# panel6.net
KiCad netlist of a schematic drawn in Altium Designer
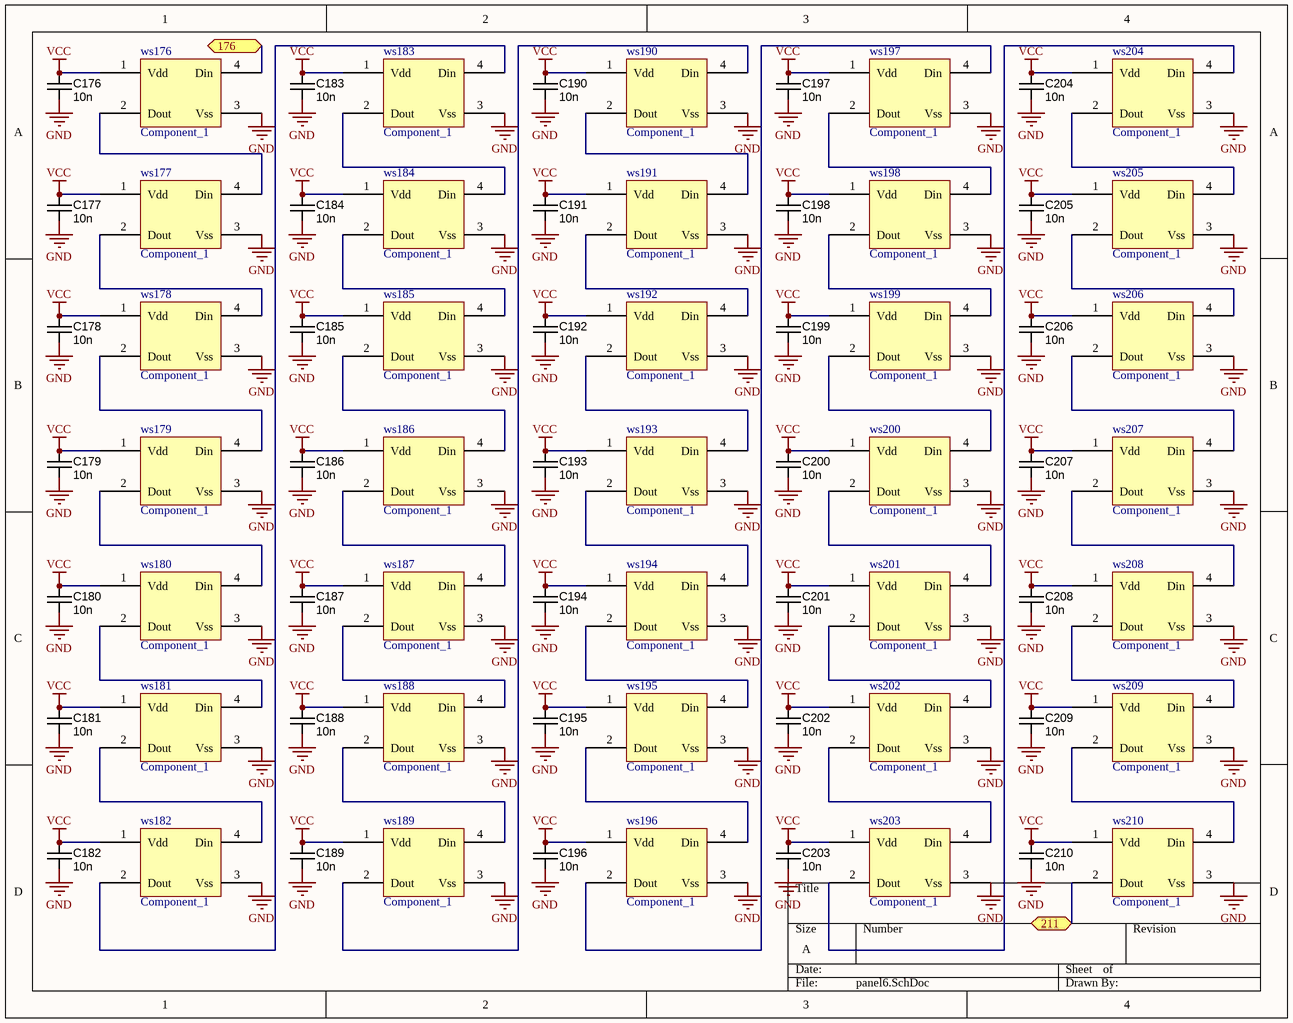
[diagram p0: panel6.SchDoc]

(export (version "E")
  (design (tool "Eeschema 10.0.6"))
  (components
    (comp (ref "C176")
      (value "10n")
      (footprint "CAPC1608X90N")
      (description "Capacitor SMD Cer 10nF 10% 100V X7R 0603")
      (fields
        (field (name "TOLERANCE") "±10%")
        (field (name "MANUFACTURER") "Murata Electronics North America")
      )
      (libsource (lib "PBL - Capacitors") (part "CAPC_10n_0603_X7R_100V_10%"))
    )
    (comp (ref "C177")
      (value "10n")
      (footprint "CAPC1608X90N")
      (description "Capacitor SMD Cer 10nF 10% 100V X7R 0603")
      (fields
        (field (name "TOLERANCE") "±10%")
        (field (name "MANUFACTURER") "Murata Electronics North America")
      )
      (libsource (lib "PBL - Capacitors") (part "CAPC_10n_0603_X7R_100V_10%"))
    )
    (comp (ref "C178")
      (value "10n")
      (footprint "CAPC1608X90N")
      (description "Capacitor SMD Cer 10nF 10% 100V X7R 0603")
      (fields
        (field (name "TOLERANCE") "±10%")
        (field (name "MANUFACTURER") "Murata Electronics North America")
      )
      (libsource (lib "PBL - Capacitors") (part "CAPC_10n_0603_X7R_100V_10%"))
    )
    (comp (ref "C179")
      (value "10n")
      (footprint "CAPC1608X90N")
      (description "Capacitor SMD Cer 10nF 10% 100V X7R 0603")
      (fields
        (field (name "TOLERANCE") "±10%")
        (field (name "MANUFACTURER") "Murata Electronics North America")
      )
      (libsource (lib "PBL - Capacitors") (part "CAPC_10n_0603_X7R_100V_10%"))
    )
    (comp (ref "C180")
      (value "10n")
      (footprint "CAPC1608X90N")
      (description "Capacitor SMD Cer 10nF 10% 100V X7R 0603")
      (fields
        (field (name "TOLERANCE") "±10%")
        (field (name "MANUFACTURER") "Murata Electronics North America")
      )
      (libsource (lib "PBL - Capacitors") (part "CAPC_10n_0603_X7R_100V_10%"))
    )
    (comp (ref "C181")
      (value "10n")
      (footprint "CAPC1608X90N")
      (description "Capacitor SMD Cer 10nF 10% 100V X7R 0603")
      (fields
        (field (name "TOLERANCE") "±10%")
        (field (name "MANUFACTURER") "Murata Electronics North America")
      )
      (libsource (lib "PBL - Capacitors") (part "CAPC_10n_0603_X7R_100V_10%"))
    )
    (comp (ref "C182")
      (value "10n")
      (footprint "CAPC1608X90N")
      (description "Capacitor SMD Cer 10nF 10% 100V X7R 0603")
      (fields
        (field (name "TOLERANCE") "±10%")
        (field (name "MANUFACTURER") "Murata Electronics North America")
      )
      (libsource (lib "PBL - Capacitors") (part "CAPC_10n_0603_X7R_100V_10%"))
    )
    (comp (ref "C183")
      (value "10n")
      (footprint "CAPC1608X90N")
      (description "Capacitor SMD Cer 10nF 10% 100V X7R 0603")
      (fields
        (field (name "TOLERANCE") "±10%")
        (field (name "MANUFACTURER") "Murata Electronics North America")
      )
      (libsource (lib "PBL - Capacitors") (part "CAPC_10n_0603_X7R_100V_10%"))
    )
    (comp (ref "C184")
      (value "10n")
      (footprint "CAPC1608X90N")
      (description "Capacitor SMD Cer 10nF 10% 100V X7R 0603")
      (fields
        (field (name "TOLERANCE") "±10%")
        (field (name "MANUFACTURER") "Murata Electronics North America")
      )
      (libsource (lib "PBL - Capacitors") (part "CAPC_10n_0603_X7R_100V_10%"))
    )
    (comp (ref "C185")
      (value "10n")
      (footprint "CAPC1608X90N")
      (description "Capacitor SMD Cer 10nF 10% 100V X7R 0603")
      (fields
        (field (name "TOLERANCE") "±10%")
        (field (name "MANUFACTURER") "Murata Electronics North America")
      )
      (libsource (lib "PBL - Capacitors") (part "CAPC_10n_0603_X7R_100V_10%"))
    )
    (comp (ref "C186")
      (value "10n")
      (footprint "CAPC1608X90N")
      (description "Capacitor SMD Cer 10nF 10% 100V X7R 0603")
      (fields
        (field (name "TOLERANCE") "±10%")
        (field (name "MANUFACTURER") "Murata Electronics North America")
      )
      (libsource (lib "PBL - Capacitors") (part "CAPC_10n_0603_X7R_100V_10%"))
    )
    (comp (ref "C187")
      (value "10n")
      (footprint "CAPC1608X90N")
      (description "Capacitor SMD Cer 10nF 10% 100V X7R 0603")
      (fields
        (field (name "TOLERANCE") "±10%")
        (field (name "MANUFACTURER") "Murata Electronics North America")
      )
      (libsource (lib "PBL - Capacitors") (part "CAPC_10n_0603_X7R_100V_10%"))
    )
    (comp (ref "C188")
      (value "10n")
      (footprint "CAPC1608X90N")
      (description "Capacitor SMD Cer 10nF 10% 100V X7R 0603")
      (fields
        (field (name "TOLERANCE") "±10%")
        (field (name "MANUFACTURER") "Murata Electronics North America")
      )
      (libsource (lib "PBL - Capacitors") (part "CAPC_10n_0603_X7R_100V_10%"))
    )
    (comp (ref "C189")
      (value "10n")
      (footprint "CAPC1608X90N")
      (description "Capacitor SMD Cer 10nF 10% 100V X7R 0603")
      (fields
        (field (name "TOLERANCE") "±10%")
        (field (name "MANUFACTURER") "Murata Electronics North America")
      )
      (libsource (lib "PBL - Capacitors") (part "CAPC_10n_0603_X7R_100V_10%"))
    )
    (comp (ref "C190")
      (value "10n")
      (footprint "CAPC1608X90N")
      (description "Capacitor SMD Cer 10nF 10% 100V X7R 0603")
      (fields
        (field (name "TOLERANCE") "±10%")
        (field (name "MANUFACTURER") "Murata Electronics North America")
      )
      (libsource (lib "PBL - Capacitors") (part "CAPC_10n_0603_X7R_100V_10%"))
    )
    (comp (ref "C191")
      (value "10n")
      (footprint "CAPC1608X90N")
      (description "Capacitor SMD Cer 10nF 10% 100V X7R 0603")
      (fields
        (field (name "TOLERANCE") "±10%")
        (field (name "MANUFACTURER") "Murata Electronics North America")
      )
      (libsource (lib "PBL - Capacitors") (part "CAPC_10n_0603_X7R_100V_10%"))
    )
    (comp (ref "C192")
      (value "10n")
      (footprint "CAPC1608X90N")
      (description "Capacitor SMD Cer 10nF 10% 100V X7R 0603")
      (fields
        (field (name "TOLERANCE") "±10%")
        (field (name "MANUFACTURER") "Murata Electronics North America")
      )
      (libsource (lib "PBL - Capacitors") (part "CAPC_10n_0603_X7R_100V_10%"))
    )
    (comp (ref "C193")
      (value "10n")
      (footprint "CAPC1608X90N")
      (description "Capacitor SMD Cer 10nF 10% 100V X7R 0603")
      (fields
        (field (name "TOLERANCE") "±10%")
        (field (name "MANUFACTURER") "Murata Electronics North America")
      )
      (libsource (lib "PBL - Capacitors") (part "CAPC_10n_0603_X7R_100V_10%"))
    )
    (comp (ref "C194")
      (value "10n")
      (footprint "CAPC1608X90N")
      (description "Capacitor SMD Cer 10nF 10% 100V X7R 0603")
      (fields
        (field (name "TOLERANCE") "±10%")
        (field (name "MANUFACTURER") "Murata Electronics North America")
      )
      (libsource (lib "PBL - Capacitors") (part "CAPC_10n_0603_X7R_100V_10%"))
    )
    (comp (ref "C195")
      (value "10n")
      (footprint "CAPC1608X90N")
      (description "Capacitor SMD Cer 10nF 10% 100V X7R 0603")
      (fields
        (field (name "TOLERANCE") "±10%")
        (field (name "MANUFACTURER") "Murata Electronics North America")
      )
      (libsource (lib "PBL - Capacitors") (part "CAPC_10n_0603_X7R_100V_10%"))
    )
    (comp (ref "C196")
      (value "10n")
      (footprint "CAPC1608X90N")
      (description "Capacitor SMD Cer 10nF 10% 100V X7R 0603")
      (fields
        (field (name "TOLERANCE") "±10%")
        (field (name "MANUFACTURER") "Murata Electronics North America")
      )
      (libsource (lib "PBL - Capacitors") (part "CAPC_10n_0603_X7R_100V_10%"))
    )
    (comp (ref "C197")
      (value "10n")
      (footprint "CAPC1608X90N")
      (description "Capacitor SMD Cer 10nF 10% 100V X7R 0603")
      (fields
        (field (name "TOLERANCE") "±10%")
        (field (name "MANUFACTURER") "Murata Electronics North America")
      )
      (libsource (lib "PBL - Capacitors") (part "CAPC_10n_0603_X7R_100V_10%"))
    )
    (comp (ref "C198")
      (value "10n")
      (footprint "CAPC1608X90N")
      (description "Capacitor SMD Cer 10nF 10% 100V X7R 0603")
      (fields
        (field (name "TOLERANCE") "±10%")
        (field (name "MANUFACTURER") "Murata Electronics North America")
      )
      (libsource (lib "PBL - Capacitors") (part "CAPC_10n_0603_X7R_100V_10%"))
    )
    (comp (ref "C199")
      (value "10n")
      (footprint "CAPC1608X90N")
      (description "Capacitor SMD Cer 10nF 10% 100V X7R 0603")
      (fields
        (field (name "TOLERANCE") "±10%")
        (field (name "MANUFACTURER") "Murata Electronics North America")
      )
      (libsource (lib "PBL - Capacitors") (part "CAPC_10n_0603_X7R_100V_10%"))
    )
    (comp (ref "C200")
      (value "10n")
      (footprint "CAPC1608X90N")
      (description "Capacitor SMD Cer 10nF 10% 100V X7R 0603")
      (fields
        (field (name "TOLERANCE") "±10%")
        (field (name "MANUFACTURER") "Murata Electronics North America")
      )
      (libsource (lib "PBL - Capacitors") (part "CAPC_10n_0603_X7R_100V_10%"))
    )
    (comp (ref "C201")
      (value "10n")
      (footprint "CAPC1608X90N")
      (description "Capacitor SMD Cer 10nF 10% 100V X7R 0603")
      (fields
        (field (name "TOLERANCE") "±10%")
        (field (name "MANUFACTURER") "Murata Electronics North America")
      )
      (libsource (lib "PBL - Capacitors") (part "CAPC_10n_0603_X7R_100V_10%"))
    )
    (comp (ref "C202")
      (value "10n")
      (footprint "CAPC1608X90N")
      (description "Capacitor SMD Cer 10nF 10% 100V X7R 0603")
      (fields
        (field (name "TOLERANCE") "±10%")
        (field (name "MANUFACTURER") "Murata Electronics North America")
      )
      (libsource (lib "PBL - Capacitors") (part "CAPC_10n_0603_X7R_100V_10%"))
    )
    (comp (ref "C203")
      (value "10n")
      (footprint "CAPC1608X90N")
      (description "Capacitor SMD Cer 10nF 10% 100V X7R 0603")
      (fields
        (field (name "TOLERANCE") "±10%")
        (field (name "MANUFACTURER") "Murata Electronics North America")
      )
      (libsource (lib "PBL - Capacitors") (part "CAPC_10n_0603_X7R_100V_10%"))
    )
    (comp (ref "C204")
      (value "10n")
      (footprint "CAPC1608X90N")
      (description "Capacitor SMD Cer 10nF 10% 100V X7R 0603")
      (fields
        (field (name "TOLERANCE") "±10%")
        (field (name "MANUFACTURER") "Murata Electronics North America")
      )
      (libsource (lib "PBL - Capacitors") (part "CAPC_10n_0603_X7R_100V_10%"))
    )
    (comp (ref "C205")
      (value "10n")
      (footprint "CAPC1608X90N")
      (description "Capacitor SMD Cer 10nF 10% 100V X7R 0603")
      (fields
        (field (name "TOLERANCE") "±10%")
        (field (name "MANUFACTURER") "Murata Electronics North America")
      )
      (libsource (lib "PBL - Capacitors") (part "CAPC_10n_0603_X7R_100V_10%"))
    )
    (comp (ref "C206")
      (value "10n")
      (footprint "CAPC1608X90N")
      (description "Capacitor SMD Cer 10nF 10% 100V X7R 0603")
      (fields
        (field (name "TOLERANCE") "±10%")
        (field (name "MANUFACTURER") "Murata Electronics North America")
      )
      (libsource (lib "PBL - Capacitors") (part "CAPC_10n_0603_X7R_100V_10%"))
    )
    (comp (ref "C207")
      (value "10n")
      (footprint "CAPC1608X90N")
      (description "Capacitor SMD Cer 10nF 10% 100V X7R 0603")
      (fields
        (field (name "TOLERANCE") "±10%")
        (field (name "MANUFACTURER") "Murata Electronics North America")
      )
      (libsource (lib "PBL - Capacitors") (part "CAPC_10n_0603_X7R_100V_10%"))
    )
    (comp (ref "C208")
      (value "10n")
      (footprint "CAPC1608X90N")
      (description "Capacitor SMD Cer 10nF 10% 100V X7R 0603")
      (fields
        (field (name "TOLERANCE") "±10%")
        (field (name "MANUFACTURER") "Murata Electronics North America")
      )
      (libsource (lib "PBL - Capacitors") (part "CAPC_10n_0603_X7R_100V_10%"))
    )
    (comp (ref "C209")
      (value "10n")
      (footprint "CAPC1608X90N")
      (description "Capacitor SMD Cer 10nF 10% 100V X7R 0603")
      (fields
        (field (name "TOLERANCE") "±10%")
        (field (name "MANUFACTURER") "Murata Electronics North America")
      )
      (libsource (lib "PBL - Capacitors") (part "CAPC_10n_0603_X7R_100V_10%"))
    )
    (comp (ref "C210")
      (value "10n")
      (footprint "CAPC1608X90N")
      (description "Capacitor SMD Cer 10nF 10% 100V X7R 0603")
      (fields
        (field (name "TOLERANCE") "±10%")
        (field (name "MANUFACTURER") "Murata Electronics North America")
      )
      (libsource (lib "PBL - Capacitors") (part "CAPC_10n_0603_X7R_100V_10%"))
    )
    (comp (ref "ws176")
      (value "Component_1")
      (footprint "SOP4")
      (libsource (lib "ws2812b") (part "Component_1"))
    )
    (comp (ref "ws177")
      (value "Component_1")
      (footprint "SOP4")
      (libsource (lib "ws2812b") (part "Component_1"))
    )
    (comp (ref "ws178")
      (value "Component_1")
      (footprint "SOP4")
      (libsource (lib "ws2812b") (part "Component_1"))
    )
    (comp (ref "ws179")
      (value "Component_1")
      (footprint "SOP4")
      (libsource (lib "ws2812b") (part "Component_1"))
    )
    (comp (ref "ws180")
      (value "Component_1")
      (footprint "SOP4")
      (libsource (lib "ws2812b") (part "Component_1"))
    )
    (comp (ref "ws181")
      (value "Component_1")
      (footprint "SOP4")
      (libsource (lib "ws2812b") (part "Component_1"))
    )
    (comp (ref "ws182")
      (value "Component_1")
      (footprint "SOP4")
      (libsource (lib "ws2812b") (part "Component_1"))
    )
    (comp (ref "ws183")
      (value "Component_1")
      (footprint "SOP4")
      (libsource (lib "ws2812b") (part "Component_1"))
    )
    (comp (ref "ws184")
      (value "Component_1")
      (footprint "SOP4")
      (libsource (lib "ws2812b") (part "Component_1"))
    )
    (comp (ref "ws185")
      (value "Component_1")
      (footprint "SOP4")
      (libsource (lib "ws2812b") (part "Component_1"))
    )
    (comp (ref "ws186")
      (value "Component_1")
      (footprint "SOP4")
      (libsource (lib "ws2812b") (part "Component_1"))
    )
    (comp (ref "ws187")
      (value "Component_1")
      (footprint "SOP4")
      (libsource (lib "ws2812b") (part "Component_1"))
    )
    (comp (ref "ws188")
      (value "Component_1")
      (footprint "SOP4")
      (libsource (lib "ws2812b") (part "Component_1"))
    )
    (comp (ref "ws189")
      (value "Component_1")
      (footprint "SOP4")
      (libsource (lib "ws2812b") (part "Component_1"))
    )
    (comp (ref "ws190")
      (value "Component_1")
      (footprint "SOP4")
      (libsource (lib "ws2812b") (part "Component_1"))
    )
    (comp (ref "ws191")
      (value "Component_1")
      (footprint "SOP4")
      (libsource (lib "ws2812b") (part "Component_1"))
    )
    (comp (ref "ws192")
      (value "Component_1")
      (footprint "SOP4")
      (libsource (lib "ws2812b") (part "Component_1"))
    )
    (comp (ref "ws193")
      (value "Component_1")
      (footprint "SOP4")
      (libsource (lib "ws2812b") (part "Component_1"))
    )
    (comp (ref "ws194")
      (value "Component_1")
      (footprint "SOP4")
      (libsource (lib "ws2812b") (part "Component_1"))
    )
    (comp (ref "ws195")
      (value "Component_1")
      (footprint "SOP4")
      (libsource (lib "ws2812b") (part "Component_1"))
    )
    (comp (ref "ws196")
      (value "Component_1")
      (footprint "SOP4")
      (libsource (lib "ws2812b") (part "Component_1"))
    )
    (comp (ref "ws197")
      (value "Component_1")
      (footprint "SOP4")
      (libsource (lib "ws2812b") (part "Component_1"))
    )
    (comp (ref "ws198")
      (value "Component_1")
      (footprint "SOP4")
      (libsource (lib "ws2812b") (part "Component_1"))
    )
    (comp (ref "ws199")
      (value "Component_1")
      (footprint "SOP4")
      (libsource (lib "ws2812b") (part "Component_1"))
    )
    (comp (ref "ws200")
      (value "Component_1")
      (footprint "SOP4")
      (libsource (lib "ws2812b") (part "Component_1"))
    )
    (comp (ref "ws201")
      (value "Component_1")
      (footprint "SOP4")
      (libsource (lib "ws2812b") (part "Component_1"))
    )
    (comp (ref "ws202")
      (value "Component_1")
      (footprint "SOP4")
      (libsource (lib "ws2812b") (part "Component_1"))
    )
    (comp (ref "ws203")
      (value "Component_1")
      (footprint "SOP4")
      (libsource (lib "ws2812b") (part "Component_1"))
    )
    (comp (ref "ws204")
      (value "Component_1")
      (footprint "SOP4")
      (libsource (lib "ws2812b") (part "Component_1"))
    )
    (comp (ref "ws205")
      (value "Component_1")
      (footprint "SOP4")
      (libsource (lib "ws2812b") (part "Component_1"))
    )
    (comp (ref "ws206")
      (value "Component_1")
      (footprint "SOP4")
      (libsource (lib "ws2812b") (part "Component_1"))
    )
    (comp (ref "ws207")
      (value "Component_1")
      (footprint "SOP4")
      (libsource (lib "ws2812b") (part "Component_1"))
    )
    (comp (ref "ws208")
      (value "Component_1")
      (footprint "SOP4")
      (libsource (lib "ws2812b") (part "Component_1"))
    )
    (comp (ref "ws209")
      (value "Component_1")
      (footprint "SOP4")
      (libsource (lib "ws2812b") (part "Component_1"))
    )
    (comp (ref "ws210")
      (value "Component_1")
      (footprint "SOP4")
      (libsource (lib "ws2812b") (part "Component_1"))
    )
  )
  (nets
    (net (code "1") (name "/176") (class "Default")
      (node (ref "ws176") (pin "4") (pinfunction "Din_4") (pintype "passive"))
    )
    (net (code "2") (name "/211") (class "Default")
      (node (ref "ws210") (pin "2") (pinfunction "Dout_2") (pintype "passive"))
    )
    (net (code "3") (name "GND") (class "Default")
      (node (ref "C176") (pin "2") (pintype "passive"))
      (node (ref "C177") (pin "2") (pintype "passive"))
      (node (ref "C178") (pin "2") (pintype "passive"))
      (node (ref "C179") (pin "2") (pintype "passive"))
      (node (ref "C180") (pin "2") (pintype "passive"))
      (node (ref "C181") (pin "2") (pintype "passive"))
      (node (ref "C182") (pin "2") (pintype "passive"))
      (node (ref "C183") (pin "2") (pintype "passive"))
      (node (ref "C184") (pin "2") (pintype "passive"))
      (node (ref "C185") (pin "2") (pintype "passive"))
      (node (ref "C186") (pin "2") (pintype "passive"))
      (node (ref "C187") (pin "2") (pintype "passive"))
      (node (ref "C188") (pin "2") (pintype "passive"))
      (node (ref "C189") (pin "2") (pintype "passive"))
      (node (ref "C190") (pin "2") (pintype "passive"))
      (node (ref "C191") (pin "2") (pintype "passive"))
      (node (ref "C192") (pin "2") (pintype "passive"))
      (node (ref "C193") (pin "2") (pintype "passive"))
      (node (ref "C194") (pin "2") (pintype "passive"))
      (node (ref "C195") (pin "2") (pintype "passive"))
      (node (ref "C196") (pin "2") (pintype "passive"))
      (node (ref "C197") (pin "2") (pintype "passive"))
      (node (ref "C198") (pin "2") (pintype "passive"))
      (node (ref "C199") (pin "2") (pintype "passive"))
      (node (ref "C200") (pin "2") (pintype "passive"))
      (node (ref "C201") (pin "2") (pintype "passive"))
      (node (ref "C202") (pin "2") (pintype "passive"))
      (node (ref "C203") (pin "2") (pintype "passive"))
      (node (ref "C204") (pin "2") (pintype "passive"))
      (node (ref "C205") (pin "2") (pintype "passive"))
      (node (ref "C206") (pin "2") (pintype "passive"))
      (node (ref "C207") (pin "2") (pintype "passive"))
      (node (ref "C208") (pin "2") (pintype "passive"))
      (node (ref "C209") (pin "2") (pintype "passive"))
      (node (ref "C210") (pin "2") (pintype "passive"))
      (node (ref "ws176") (pin "3") (pinfunction "Vss_3") (pintype "passive"))
      (node (ref "ws177") (pin "3") (pinfunction "Vss_3") (pintype "passive"))
      (node (ref "ws178") (pin "3") (pinfunction "Vss_3") (pintype "passive"))
      (node (ref "ws179") (pin "3") (pinfunction "Vss_3") (pintype "passive"))
      (node (ref "ws180") (pin "3") (pinfunction "Vss_3") (pintype "passive"))
      (node (ref "ws181") (pin "3") (pinfunction "Vss_3") (pintype "passive"))
      (node (ref "ws182") (pin "3") (pinfunction "Vss_3") (pintype "passive"))
      (node (ref "ws183") (pin "3") (pinfunction "Vss_3") (pintype "passive"))
      (node (ref "ws184") (pin "3") (pinfunction "Vss_3") (pintype "passive"))
      (node (ref "ws185") (pin "3") (pinfunction "Vss_3") (pintype "passive"))
      (node (ref "ws186") (pin "3") (pinfunction "Vss_3") (pintype "passive"))
      (node (ref "ws187") (pin "3") (pinfunction "Vss_3") (pintype "passive"))
      (node (ref "ws188") (pin "3") (pinfunction "Vss_3") (pintype "passive"))
      (node (ref "ws189") (pin "3") (pinfunction "Vss_3") (pintype "passive"))
      (node (ref "ws190") (pin "3") (pinfunction "Vss_3") (pintype "passive"))
      (node (ref "ws191") (pin "3") (pinfunction "Vss_3") (pintype "passive"))
      (node (ref "ws192") (pin "3") (pinfunction "Vss_3") (pintype "passive"))
      (node (ref "ws193") (pin "3") (pinfunction "Vss_3") (pintype "passive"))
      (node (ref "ws194") (pin "3") (pinfunction "Vss_3") (pintype "passive"))
      (node (ref "ws195") (pin "3") (pinfunction "Vss_3") (pintype "passive"))
      (node (ref "ws196") (pin "3") (pinfunction "Vss_3") (pintype "passive"))
      (node (ref "ws197") (pin "3") (pinfunction "Vss_3") (pintype "passive"))
      (node (ref "ws198") (pin "3") (pinfunction "Vss_3") (pintype "passive"))
      (node (ref "ws199") (pin "3") (pinfunction "Vss_3") (pintype "passive"))
      (node (ref "ws200") (pin "3") (pinfunction "Vss_3") (pintype "passive"))
      (node (ref "ws201") (pin "3") (pinfunction "Vss_3") (pintype "passive"))
      (node (ref "ws202") (pin "3") (pinfunction "Vss_3") (pintype "passive"))
      (node (ref "ws203") (pin "3") (pinfunction "Vss_3") (pintype "passive"))
      (node (ref "ws204") (pin "3") (pinfunction "Vss_3") (pintype "passive"))
      (node (ref "ws205") (pin "3") (pinfunction "Vss_3") (pintype "passive"))
      (node (ref "ws206") (pin "3") (pinfunction "Vss_3") (pintype "passive"))
      (node (ref "ws207") (pin "3") (pinfunction "Vss_3") (pintype "passive"))
      (node (ref "ws208") (pin "3") (pinfunction "Vss_3") (pintype "passive"))
      (node (ref "ws209") (pin "3") (pinfunction "Vss_3") (pintype "passive"))
      (node (ref "ws210") (pin "3") (pinfunction "Vss_3") (pintype "passive"))
    )
    (net (code "4") (name "Net-(ws176-Dout)") (class "Default")
      (node (ref "ws176") (pin "2") (pinfunction "Dout_2") (pintype "passive"))
      (node (ref "ws177") (pin "4") (pinfunction "Din_4") (pintype "passive"))
    )
    (net (code "5") (name "Net-(ws177-Dout)") (class "Default")
      (node (ref "ws177") (pin "2") (pinfunction "Dout_2") (pintype "passive"))
      (node (ref "ws178") (pin "4") (pinfunction "Din_4") (pintype "passive"))
    )
    (net (code "6") (name "Net-(ws178-Dout)") (class "Default")
      (node (ref "ws178") (pin "2") (pinfunction "Dout_2") (pintype "passive"))
      (node (ref "ws179") (pin "4") (pinfunction "Din_4") (pintype "passive"))
    )
    (net (code "7") (name "Net-(ws179-Dout)") (class "Default")
      (node (ref "ws179") (pin "2") (pinfunction "Dout_2") (pintype "passive"))
      (node (ref "ws180") (pin "4") (pinfunction "Din_4") (pintype "passive"))
    )
    (net (code "8") (name "Net-(ws180-Dout)") (class "Default")
      (node (ref "ws180") (pin "2") (pinfunction "Dout_2") (pintype "passive"))
      (node (ref "ws181") (pin "4") (pinfunction "Din_4") (pintype "passive"))
    )
    (net (code "9") (name "Net-(ws181-Dout)") (class "Default")
      (node (ref "ws181") (pin "2") (pinfunction "Dout_2") (pintype "passive"))
      (node (ref "ws182") (pin "4") (pinfunction "Din_4") (pintype "passive"))
    )
    (net (code "10") (name "Net-(ws182-Dout)") (class "Default")
      (node (ref "ws182") (pin "2") (pinfunction "Dout_2") (pintype "passive"))
      (node (ref "ws183") (pin "4") (pinfunction "Din_4") (pintype "passive"))
    )
    (net (code "11") (name "Net-(ws183-Dout)") (class "Default")
      (node (ref "ws183") (pin "2") (pinfunction "Dout_2") (pintype "passive"))
      (node (ref "ws184") (pin "4") (pinfunction "Din_4") (pintype "passive"))
    )
    (net (code "12") (name "Net-(ws184-Dout)") (class "Default")
      (node (ref "ws184") (pin "2") (pinfunction "Dout_2") (pintype "passive"))
      (node (ref "ws185") (pin "4") (pinfunction "Din_4") (pintype "passive"))
    )
    (net (code "13") (name "Net-(ws185-Dout)") (class "Default")
      (node (ref "ws185") (pin "2") (pinfunction "Dout_2") (pintype "passive"))
      (node (ref "ws186") (pin "4") (pinfunction "Din_4") (pintype "passive"))
    )
    (net (code "14") (name "Net-(ws186-Dout)") (class "Default")
      (node (ref "ws186") (pin "2") (pinfunction "Dout_2") (pintype "passive"))
      (node (ref "ws187") (pin "4") (pinfunction "Din_4") (pintype "passive"))
    )
    (net (code "15") (name "Net-(ws187-Dout)") (class "Default")
      (node (ref "ws187") (pin "2") (pinfunction "Dout_2") (pintype "passive"))
      (node (ref "ws188") (pin "4") (pinfunction "Din_4") (pintype "passive"))
    )
    (net (code "16") (name "Net-(ws188-Dout)") (class "Default")
      (node (ref "ws188") (pin "2") (pinfunction "Dout_2") (pintype "passive"))
      (node (ref "ws189") (pin "4") (pinfunction "Din_4") (pintype "passive"))
    )
    (net (code "17") (name "Net-(ws189-Dout)") (class "Default")
      (node (ref "ws189") (pin "2") (pinfunction "Dout_2") (pintype "passive"))
      (node (ref "ws190") (pin "4") (pinfunction "Din_4") (pintype "passive"))
    )
    (net (code "18") (name "Net-(ws190-Dout)") (class "Default")
      (node (ref "ws190") (pin "2") (pinfunction "Dout_2") (pintype "passive"))
      (node (ref "ws191") (pin "4") (pinfunction "Din_4") (pintype "passive"))
    )
    (net (code "19") (name "Net-(ws191-Dout)") (class "Default")
      (node (ref "ws191") (pin "2") (pinfunction "Dout_2") (pintype "passive"))
      (node (ref "ws192") (pin "4") (pinfunction "Din_4") (pintype "passive"))
    )
    (net (code "20") (name "Net-(ws192-Dout)") (class "Default")
      (node (ref "ws192") (pin "2") (pinfunction "Dout_2") (pintype "passive"))
      (node (ref "ws193") (pin "4") (pinfunction "Din_4") (pintype "passive"))
    )
    (net (code "21") (name "Net-(ws193-Dout)") (class "Default")
      (node (ref "ws193") (pin "2") (pinfunction "Dout_2") (pintype "passive"))
      (node (ref "ws194") (pin "4") (pinfunction "Din_4") (pintype "passive"))
    )
    (net (code "22") (name "Net-(ws194-Dout)") (class "Default")
      (node (ref "ws194") (pin "2") (pinfunction "Dout_2") (pintype "passive"))
      (node (ref "ws195") (pin "4") (pinfunction "Din_4") (pintype "passive"))
    )
    (net (code "23") (name "Net-(ws195-Dout)") (class "Default")
      (node (ref "ws195") (pin "2") (pinfunction "Dout_2") (pintype "passive"))
      (node (ref "ws196") (pin "4") (pinfunction "Din_4") (pintype "passive"))
    )
    (net (code "24") (name "Net-(ws196-Dout)") (class "Default")
      (node (ref "ws196") (pin "2") (pinfunction "Dout_2") (pintype "passive"))
      (node (ref "ws197") (pin "4") (pinfunction "Din_4") (pintype "passive"))
    )
    (net (code "25") (name "Net-(ws197-Dout)") (class "Default")
      (node (ref "ws197") (pin "2") (pinfunction "Dout_2") (pintype "passive"))
      (node (ref "ws198") (pin "4") (pinfunction "Din_4") (pintype "passive"))
    )
    (net (code "26") (name "Net-(ws198-Dout)") (class "Default")
      (node (ref "ws198") (pin "2") (pinfunction "Dout_2") (pintype "passive"))
      (node (ref "ws199") (pin "4") (pinfunction "Din_4") (pintype "passive"))
    )
    (net (code "27") (name "Net-(ws199-Dout)") (class "Default")
      (node (ref "ws199") (pin "2") (pinfunction "Dout_2") (pintype "passive"))
      (node (ref "ws200") (pin "4") (pinfunction "Din_4") (pintype "passive"))
    )
    (net (code "28") (name "Net-(ws200-Dout)") (class "Default")
      (node (ref "ws200") (pin "2") (pinfunction "Dout_2") (pintype "passive"))
      (node (ref "ws201") (pin "4") (pinfunction "Din_4") (pintype "passive"))
    )
    (net (code "29") (name "Net-(ws201-Dout)") (class "Default")
      (node (ref "ws201") (pin "2") (pinfunction "Dout_2") (pintype "passive"))
      (node (ref "ws202") (pin "4") (pinfunction "Din_4") (pintype "passive"))
    )
    (net (code "30") (name "Net-(ws202-Dout)") (class "Default")
      (node (ref "ws202") (pin "2") (pinfunction "Dout_2") (pintype "passive"))
      (node (ref "ws203") (pin "4") (pinfunction "Din_4") (pintype "passive"))
    )
    (net (code "31") (name "Net-(ws203-Dout)") (class "Default")
      (node (ref "ws203") (pin "2") (pinfunction "Dout_2") (pintype "passive"))
      (node (ref "ws204") (pin "4") (pinfunction "Din_4") (pintype "passive"))
    )
    (net (code "32") (name "Net-(ws204-Dout)") (class "Default")
      (node (ref "ws204") (pin "2") (pinfunction "Dout_2") (pintype "passive"))
      (node (ref "ws205") (pin "4") (pinfunction "Din_4") (pintype "passive"))
    )
    (net (code "33") (name "Net-(ws205-Dout)") (class "Default")
      (node (ref "ws205") (pin "2") (pinfunction "Dout_2") (pintype "passive"))
      (node (ref "ws206") (pin "4") (pinfunction "Din_4") (pintype "passive"))
    )
    (net (code "34") (name "Net-(ws206-Dout)") (class "Default")
      (node (ref "ws206") (pin "2") (pinfunction "Dout_2") (pintype "passive"))
      (node (ref "ws207") (pin "4") (pinfunction "Din_4") (pintype "passive"))
    )
    (net (code "35") (name "Net-(ws207-Dout)") (class "Default")
      (node (ref "ws207") (pin "2") (pinfunction "Dout_2") (pintype "passive"))
      (node (ref "ws208") (pin "4") (pinfunction "Din_4") (pintype "passive"))
    )
    (net (code "36") (name "Net-(ws208-Dout)") (class "Default")
      (node (ref "ws208") (pin "2") (pinfunction "Dout_2") (pintype "passive"))
      (node (ref "ws209") (pin "4") (pinfunction "Din_4") (pintype "passive"))
    )
    (net (code "37") (name "Net-(ws209-Dout)") (class "Default")
      (node (ref "ws209") (pin "2") (pinfunction "Dout_2") (pintype "passive"))
      (node (ref "ws210") (pin "4") (pinfunction "Din_4") (pintype "passive"))
    )
    (net (code "38") (name "VCC") (class "Default")
      (node (ref "C176") (pin "1") (pintype "passive"))
      (node (ref "C177") (pin "1") (pintype "passive"))
      (node (ref "C178") (pin "1") (pintype "passive"))
      (node (ref "C179") (pin "1") (pintype "passive"))
      (node (ref "C180") (pin "1") (pintype "passive"))
      (node (ref "C181") (pin "1") (pintype "passive"))
      (node (ref "C182") (pin "1") (pintype "passive"))
      (node (ref "C183") (pin "1") (pintype "passive"))
      (node (ref "C184") (pin "1") (pintype "passive"))
      (node (ref "C185") (pin "1") (pintype "passive"))
      (node (ref "C186") (pin "1") (pintype "passive"))
      (node (ref "C187") (pin "1") (pintype "passive"))
      (node (ref "C188") (pin "1") (pintype "passive"))
      (node (ref "C189") (pin "1") (pintype "passive"))
      (node (ref "C190") (pin "1") (pintype "passive"))
      (node (ref "C191") (pin "1") (pintype "passive"))
      (node (ref "C192") (pin "1") (pintype "passive"))
      (node (ref "C193") (pin "1") (pintype "passive"))
      (node (ref "C194") (pin "1") (pintype "passive"))
      (node (ref "C195") (pin "1") (pintype "passive"))
      (node (ref "C196") (pin "1") (pintype "passive"))
      (node (ref "C197") (pin "1") (pintype "passive"))
      (node (ref "C198") (pin "1") (pintype "passive"))
      (node (ref "C199") (pin "1") (pintype "passive"))
      (node (ref "C200") (pin "1") (pintype "passive"))
      (node (ref "C201") (pin "1") (pintype "passive"))
      (node (ref "C202") (pin "1") (pintype "passive"))
      (node (ref "C203") (pin "1") (pintype "passive"))
      (node (ref "C204") (pin "1") (pintype "passive"))
      (node (ref "C205") (pin "1") (pintype "passive"))
      (node (ref "C206") (pin "1") (pintype "passive"))
      (node (ref "C207") (pin "1") (pintype "passive"))
      (node (ref "C208") (pin "1") (pintype "passive"))
      (node (ref "C209") (pin "1") (pintype "passive"))
      (node (ref "C210") (pin "1") (pintype "passive"))
      (node (ref "ws176") (pin "1") (pinfunction "Vdd_1") (pintype "passive"))
      (node (ref "ws177") (pin "1") (pinfunction "Vdd_1") (pintype "passive"))
      (node (ref "ws178") (pin "1") (pinfunction "Vdd_1") (pintype "passive"))
      (node (ref "ws179") (pin "1") (pinfunction "Vdd_1") (pintype "passive"))
      (node (ref "ws180") (pin "1") (pinfunction "Vdd_1") (pintype "passive"))
      (node (ref "ws181") (pin "1") (pinfunction "Vdd_1") (pintype "passive"))
      (node (ref "ws182") (pin "1") (pinfunction "Vdd_1") (pintype "passive"))
      (node (ref "ws183") (pin "1") (pinfunction "Vdd_1") (pintype "passive"))
      (node (ref "ws184") (pin "1") (pinfunction "Vdd_1") (pintype "passive"))
      (node (ref "ws185") (pin "1") (pinfunction "Vdd_1") (pintype "passive"))
      (node (ref "ws186") (pin "1") (pinfunction "Vdd_1") (pintype "passive"))
      (node (ref "ws187") (pin "1") (pinfunction "Vdd_1") (pintype "passive"))
      (node (ref "ws188") (pin "1") (pinfunction "Vdd_1") (pintype "passive"))
      (node (ref "ws189") (pin "1") (pinfunction "Vdd_1") (pintype "passive"))
      (node (ref "ws190") (pin "1") (pinfunction "Vdd_1") (pintype "passive"))
      (node (ref "ws191") (pin "1") (pinfunction "Vdd_1") (pintype "passive"))
      (node (ref "ws192") (pin "1") (pinfunction "Vdd_1") (pintype "passive"))
      (node (ref "ws193") (pin "1") (pinfunction "Vdd_1") (pintype "passive"))
      (node (ref "ws194") (pin "1") (pinfunction "Vdd_1") (pintype "passive"))
      (node (ref "ws195") (pin "1") (pinfunction "Vdd_1") (pintype "passive"))
      (node (ref "ws196") (pin "1") (pinfunction "Vdd_1") (pintype "passive"))
      (node (ref "ws197") (pin "1") (pinfunction "Vdd_1") (pintype "passive"))
      (node (ref "ws198") (pin "1") (pinfunction "Vdd_1") (pintype "passive"))
      (node (ref "ws199") (pin "1") (pinfunction "Vdd_1") (pintype "passive"))
      (node (ref "ws200") (pin "1") (pinfunction "Vdd_1") (pintype "passive"))
      (node (ref "ws201") (pin "1") (pinfunction "Vdd_1") (pintype "passive"))
      (node (ref "ws202") (pin "1") (pinfunction "Vdd_1") (pintype "passive"))
      (node (ref "ws203") (pin "1") (pinfunction "Vdd_1") (pintype "passive"))
      (node (ref "ws204") (pin "1") (pinfunction "Vdd_1") (pintype "passive"))
      (node (ref "ws205") (pin "1") (pinfunction "Vdd_1") (pintype "passive"))
      (node (ref "ws206") (pin "1") (pinfunction "Vdd_1") (pintype "passive"))
      (node (ref "ws207") (pin "1") (pinfunction "Vdd_1") (pintype "passive"))
      (node (ref "ws208") (pin "1") (pinfunction "Vdd_1") (pintype "passive"))
      (node (ref "ws209") (pin "1") (pinfunction "Vdd_1") (pintype "passive"))
      (node (ref "ws210") (pin "1") (pinfunction "Vdd_1") (pintype "passive"))
    )
  )
)
